# sensorboard_atm_rev1.net
KiCad netlist of a schematic drawn in EAGLE
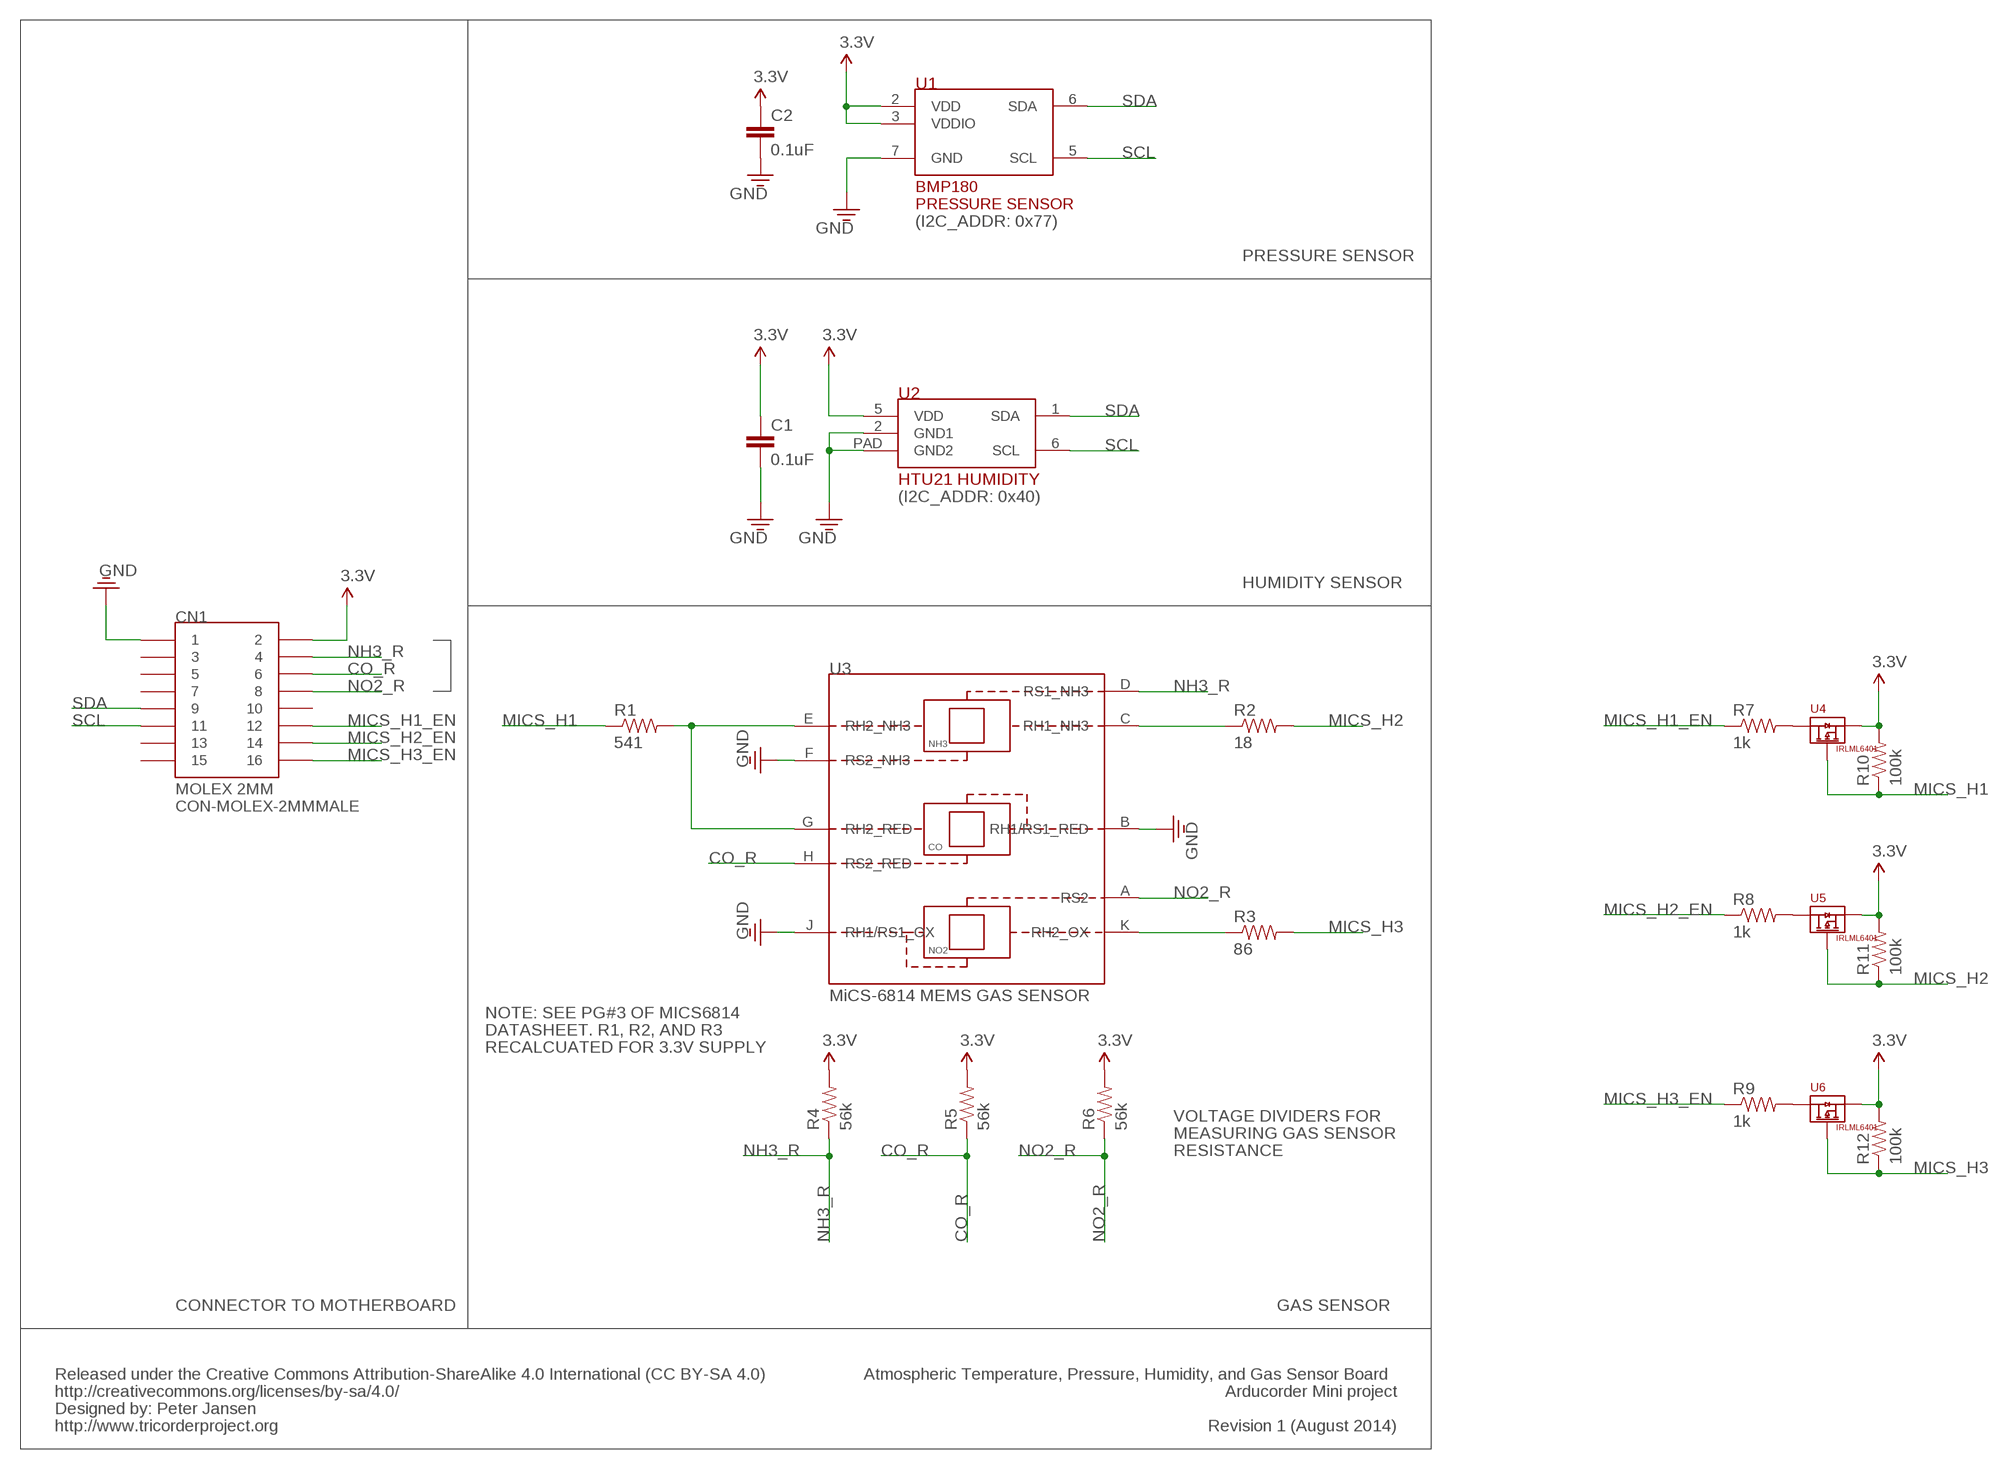
[diagram p0: schematic, sheet 1]

(export (version "E")
  (design (tool "Eeschema 10.0.6"))
  (components
    (comp (ref "C1")
      (value "0.1uF")
      (footprint "eagle-import:0603")
      (libsource (lib "eagle-import") (part "CAP0603"))
    )
    (comp (ref "C2")
      (value "0.1uF")
      (footprint "eagle-import:0603")
      (libsource (lib "eagle-import") (part "CAP0603"))
    )
    (comp (ref "CN1")
      (value "CON-MOLEX-2MMMALE")
      (footprint "eagle-import:MOLEX-0877591650")
      (libsource (lib "eagle-import") (part "CON-MOLEX-2MMMALE"))
    )
    (comp (ref "R1")
      (value "541")
      (footprint "eagle-import:0603")
      (libsource (lib "eagle-import") (part "RESISTOR0603"))
    )
    (comp (ref "R2")
      (value "18")
      (footprint "eagle-import:0603")
      (libsource (lib "eagle-import") (part "RESISTOR0603"))
    )
    (comp (ref "R3")
      (value "86")
      (footprint "eagle-import:0603")
      (libsource (lib "eagle-import") (part "RESISTOR0603"))
    )
    (comp (ref "R4")
      (value "56k")
      (footprint "eagle-import:0603")
      (libsource (lib "eagle-import") (part "RESISTOR0603"))
    )
    (comp (ref "R5")
      (value "56k")
      (footprint "eagle-import:0603")
      (libsource (lib "eagle-import") (part "RESISTOR0603"))
    )
    (comp (ref "R6")
      (value "56k")
      (footprint "eagle-import:0603")
      (libsource (lib "eagle-import") (part "RESISTOR0603"))
    )
    (comp (ref "R7")
      (value "1k")
      (footprint "eagle-import:0603")
      (libsource (lib "eagle-import") (part "RESISTOR0603"))
    )
    (comp (ref "R8")
      (value "1k")
      (footprint "eagle-import:0603")
      (libsource (lib "eagle-import") (part "RESISTOR0603"))
    )
    (comp (ref "R9")
      (value "1k")
      (footprint "eagle-import:0603")
      (libsource (lib "eagle-import") (part "RESISTOR0603"))
    )
    (comp (ref "R10")
      (value "100k")
      (footprint "eagle-import:0603")
      (libsource (lib "eagle-import") (part "RESISTOR0603"))
    )
    (comp (ref "R11")
      (value "100k")
      (footprint "eagle-import:0603")
      (libsource (lib "eagle-import") (part "RESISTOR0603"))
    )
    (comp (ref "R12")
      (value "100k")
      (footprint "eagle-import:0603")
      (libsource (lib "eagle-import") (part "RESISTOR0603"))
    )
    (comp (ref "U1")
      (value "BMP180")
      (footprint "eagle-import:BMP180")
      (libsource (lib "eagle-import") (part "BMP180"))
    )
    (comp (ref "U2")
      (value "HTU21D")
      (footprint "eagle-import:HTU21D")
      (libsource (lib "eagle-import") (part "HTU21D"))
    )
    (comp (ref "U3")
      (value "MICS-6814")
      (footprint "eagle-import:MICS-6814")
      (libsource (lib "eagle-import") (part "MICS-6814"))
    )
    (comp (ref "U4")
      (value "MOSFET-IRLML6401")
      (footprint "eagle-import:SOT23-3L")
      (libsource (lib "eagle-import") (part "MOSFET-IRLML6401"))
    )
    (comp (ref "U5")
      (value "MOSFET-IRLML6401")
      (footprint "eagle-import:SOT23-3L")
      (libsource (lib "eagle-import") (part "MOSFET-IRLML6401"))
    )
    (comp (ref "U6")
      (value "MOSFET-IRLML6401")
      (footprint "eagle-import:SOT23-3L")
      (libsource (lib "eagle-import") (part "MOSFET-IRLML6401"))
    )
  )
  (nets
    (net (code "1") (name "/CO_R") (class "Default")
      (node (ref "CN1") (pin "6") (pinfunction "6_6") (pintype "bidirectional"))
      (node (ref "R5") (pin "1") (pinfunction "1_1") (pintype "passive"))
      (node (ref "U3") (pin "H") (pinfunction "RS2_RED_H") (pintype "bidirectional"))
    )
    (net (code "2") (name "/MICS_H1") (class "Default")
      (node (ref "R1") (pin "1") (pinfunction "1_1") (pintype "passive"))
      (node (ref "R10") (pin "1") (pinfunction "1_1") (pintype "passive"))
      (node (ref "U4") (pin "1") (pinfunction "G_1") (pintype "bidirectional"))
    )
    (net (code "3") (name "/MICS_H1_EN") (class "Default")
      (node (ref "CN1") (pin "12") (pinfunction "12_12") (pintype "bidirectional"))
      (node (ref "R7") (pin "1") (pinfunction "1_1") (pintype "passive"))
    )
    (net (code "4") (name "/MICS_H2") (class "Default")
      (node (ref "R11") (pin "1") (pinfunction "1_1") (pintype "passive"))
      (node (ref "R2") (pin "2") (pinfunction "2_2") (pintype "passive"))
      (node (ref "U5") (pin "1") (pinfunction "G_1") (pintype "bidirectional"))
    )
    (net (code "5") (name "/MICS_H2_EN") (class "Default")
      (node (ref "CN1") (pin "14") (pinfunction "14_14") (pintype "bidirectional"))
      (node (ref "R8") (pin "1") (pinfunction "1_1") (pintype "passive"))
    )
    (net (code "6") (name "/MICS_H3") (class "Default")
      (node (ref "R12") (pin "1") (pinfunction "1_1") (pintype "passive"))
      (node (ref "R3") (pin "2") (pinfunction "2_2") (pintype "passive"))
      (node (ref "U6") (pin "1") (pinfunction "G_1") (pintype "bidirectional"))
    )
    (net (code "7") (name "/MICS_H3_EN") (class "Default")
      (node (ref "CN1") (pin "16") (pinfunction "16_16") (pintype "bidirectional"))
      (node (ref "R9") (pin "1") (pinfunction "1_1") (pintype "passive"))
    )
    (net (code "8") (name "/NH3_R") (class "Default")
      (node (ref "CN1") (pin "4") (pinfunction "4_4") (pintype "bidirectional"))
      (node (ref "R4") (pin "1") (pinfunction "1_1") (pintype "passive"))
      (node (ref "U3") (pin "D") (pinfunction "RS1_NH3_D") (pintype "bidirectional"))
    )
    (net (code "9") (name "/NO2_R") (class "Default")
      (node (ref "CN1") (pin "8") (pinfunction "8_8") (pintype "bidirectional"))
      (node (ref "R6") (pin "1") (pinfunction "1_1") (pintype "passive"))
      (node (ref "U3") (pin "A") (pinfunction "RS2_A") (pintype "bidirectional"))
    )
    (net (code "10") (name "/SCL") (class "Default")
      (node (ref "CN1") (pin "11") (pinfunction "11_11") (pintype "bidirectional"))
      (node (ref "U1") (pin "5") (pinfunction "SCL_5") (pintype "bidirectional"))
      (node (ref "U2") (pin "6") (pinfunction "SCL_6") (pintype "bidirectional"))
    )
    (net (code "11") (name "/SDA") (class "Default")
      (node (ref "CN1") (pin "9") (pinfunction "9_9") (pintype "bidirectional"))
      (node (ref "U1") (pin "6") (pinfunction "SDA_6") (pintype "bidirectional"))
      (node (ref "U2") (pin "1") (pinfunction "SDA_1") (pintype "bidirectional"))
    )
    (net (code "12") (name "3.3V") (class "Default")
      (node (ref "C1") (pin "1") (pinfunction "1_1") (pintype "passive"))
      (node (ref "C2") (pin "1") (pinfunction "1_1") (pintype "passive"))
      (node (ref "CN1") (pin "2") (pinfunction "2_2") (pintype "bidirectional"))
      (node (ref "R10") (pin "2") (pinfunction "2_2") (pintype "passive"))
      (node (ref "R11") (pin "2") (pinfunction "2_2") (pintype "passive"))
      (node (ref "R12") (pin "2") (pinfunction "2_2") (pintype "passive"))
      (node (ref "R4") (pin "2") (pinfunction "2_2") (pintype "passive"))
      (node (ref "R5") (pin "2") (pinfunction "2_2") (pintype "passive"))
      (node (ref "R6") (pin "2") (pinfunction "2_2") (pintype "passive"))
      (node (ref "U1") (pin "2") (pinfunction "VDD_2") (pintype "bidirectional"))
      (node (ref "U1") (pin "3") (pinfunction "VDDIO_3") (pintype "bidirectional"))
      (node (ref "U2") (pin "5") (pinfunction "VDD_5") (pintype "bidirectional"))
      (node (ref "U4") (pin "2") (pinfunction "S_2") (pintype "bidirectional"))
      (node (ref "U5") (pin "2") (pinfunction "S_2") (pintype "bidirectional"))
      (node (ref "U6") (pin "2") (pinfunction "S_2") (pintype "bidirectional"))
    )
    (net (code "13") (name "GND") (class "Default")
      (node (ref "C1") (pin "2") (pinfunction "2_2") (pintype "passive"))
      (node (ref "C2") (pin "2") (pinfunction "2_2") (pintype "passive"))
      (node (ref "CN1") (pin "1") (pinfunction "1_1") (pintype "bidirectional"))
      (node (ref "U1") (pin "7") (pinfunction "GND_7") (pintype "bidirectional"))
      (node (ref "U2") (pin "2") (pinfunction "GND1_2") (pintype "bidirectional"))
      (node (ref "U2") (pin "PAD") (pinfunction "GND2_PAD") (pintype "bidirectional"))
      (node (ref "U3") (pin "B") (pinfunction "RH1/RS1_RED_B") (pintype "bidirectional"))
      (node (ref "U3") (pin "F") (pinfunction "RS2_NH3_F") (pintype "bidirectional"))
      (node (ref "U3") (pin "J") (pinfunction "RH1/RS1_OX_J") (pintype "bidirectional"))
    )
    (net (code "14") (name "Net-(U3-RH1_NH3)") (class "Default")
      (node (ref "R2") (pin "1") (pinfunction "1_1") (pintype "passive"))
      (node (ref "U3") (pin "C") (pinfunction "RH1_NH3_C") (pintype "bidirectional"))
    )
    (net (code "15") (name "Net-(U3-RH2_NH3)") (class "Default")
      (node (ref "R1") (pin "2") (pinfunction "2_2") (pintype "passive"))
      (node (ref "U3") (pin "E") (pinfunction "RH2_NH3_E") (pintype "bidirectional"))
      (node (ref "U3") (pin "G") (pinfunction "RH2_RED_G") (pintype "bidirectional"))
    )
    (net (code "16") (name "Net-(U3-RH2_OX)") (class "Default")
      (node (ref "R3") (pin "1") (pinfunction "1_1") (pintype "passive"))
      (node (ref "U3") (pin "K") (pinfunction "RH2_OX_K") (pintype "bidirectional"))
    )
    (net (code "17") (name "Net-(U4-D)") (class "Default")
      (node (ref "R7") (pin "2") (pinfunction "2_2") (pintype "passive"))
      (node (ref "U4") (pin "3") (pinfunction "D_3") (pintype "bidirectional"))
    )
    (net (code "18") (name "Net-(U5-D)") (class "Default")
      (node (ref "R8") (pin "2") (pinfunction "2_2") (pintype "passive"))
      (node (ref "U5") (pin "3") (pinfunction "D_3") (pintype "bidirectional"))
    )
    (net (code "19") (name "Net-(U6-D)") (class "Default")
      (node (ref "R9") (pin "2") (pinfunction "2_2") (pintype "passive"))
      (node (ref "U6") (pin "3") (pinfunction "D_3") (pintype "bidirectional"))
    )
    (net (code "20") (name "unconnected-(CN1-Pad3)") (class "Default")
      (node (ref "CN1") (pin "3") (pinfunction "3_3") (pintype "bidirectional"))
    )
    (net (code "21") (name "unconnected-(CN1-Pad5)") (class "Default")
      (node (ref "CN1") (pin "5") (pinfunction "5_5") (pintype "bidirectional"))
    )
    (net (code "22") (name "unconnected-(CN1-Pad7)") (class "Default")
      (node (ref "CN1") (pin "7") (pinfunction "7_7") (pintype "bidirectional"))
    )
    (net (code "23") (name "unconnected-(CN1-Pad10)") (class "Default")
      (node (ref "CN1") (pin "10") (pinfunction "10_10") (pintype "bidirectional"))
    )
    (net (code "24") (name "unconnected-(CN1-Pad13)") (class "Default")
      (node (ref "CN1") (pin "13") (pinfunction "13_13") (pintype "bidirectional"))
    )
    (net (code "25") (name "unconnected-(CN1-Pad15)") (class "Default")
      (node (ref "CN1") (pin "15") (pinfunction "15_15") (pintype "bidirectional"))
    )
  )
)
